# main.net
KiCad netlist of a schematic drawn in Altium Designer
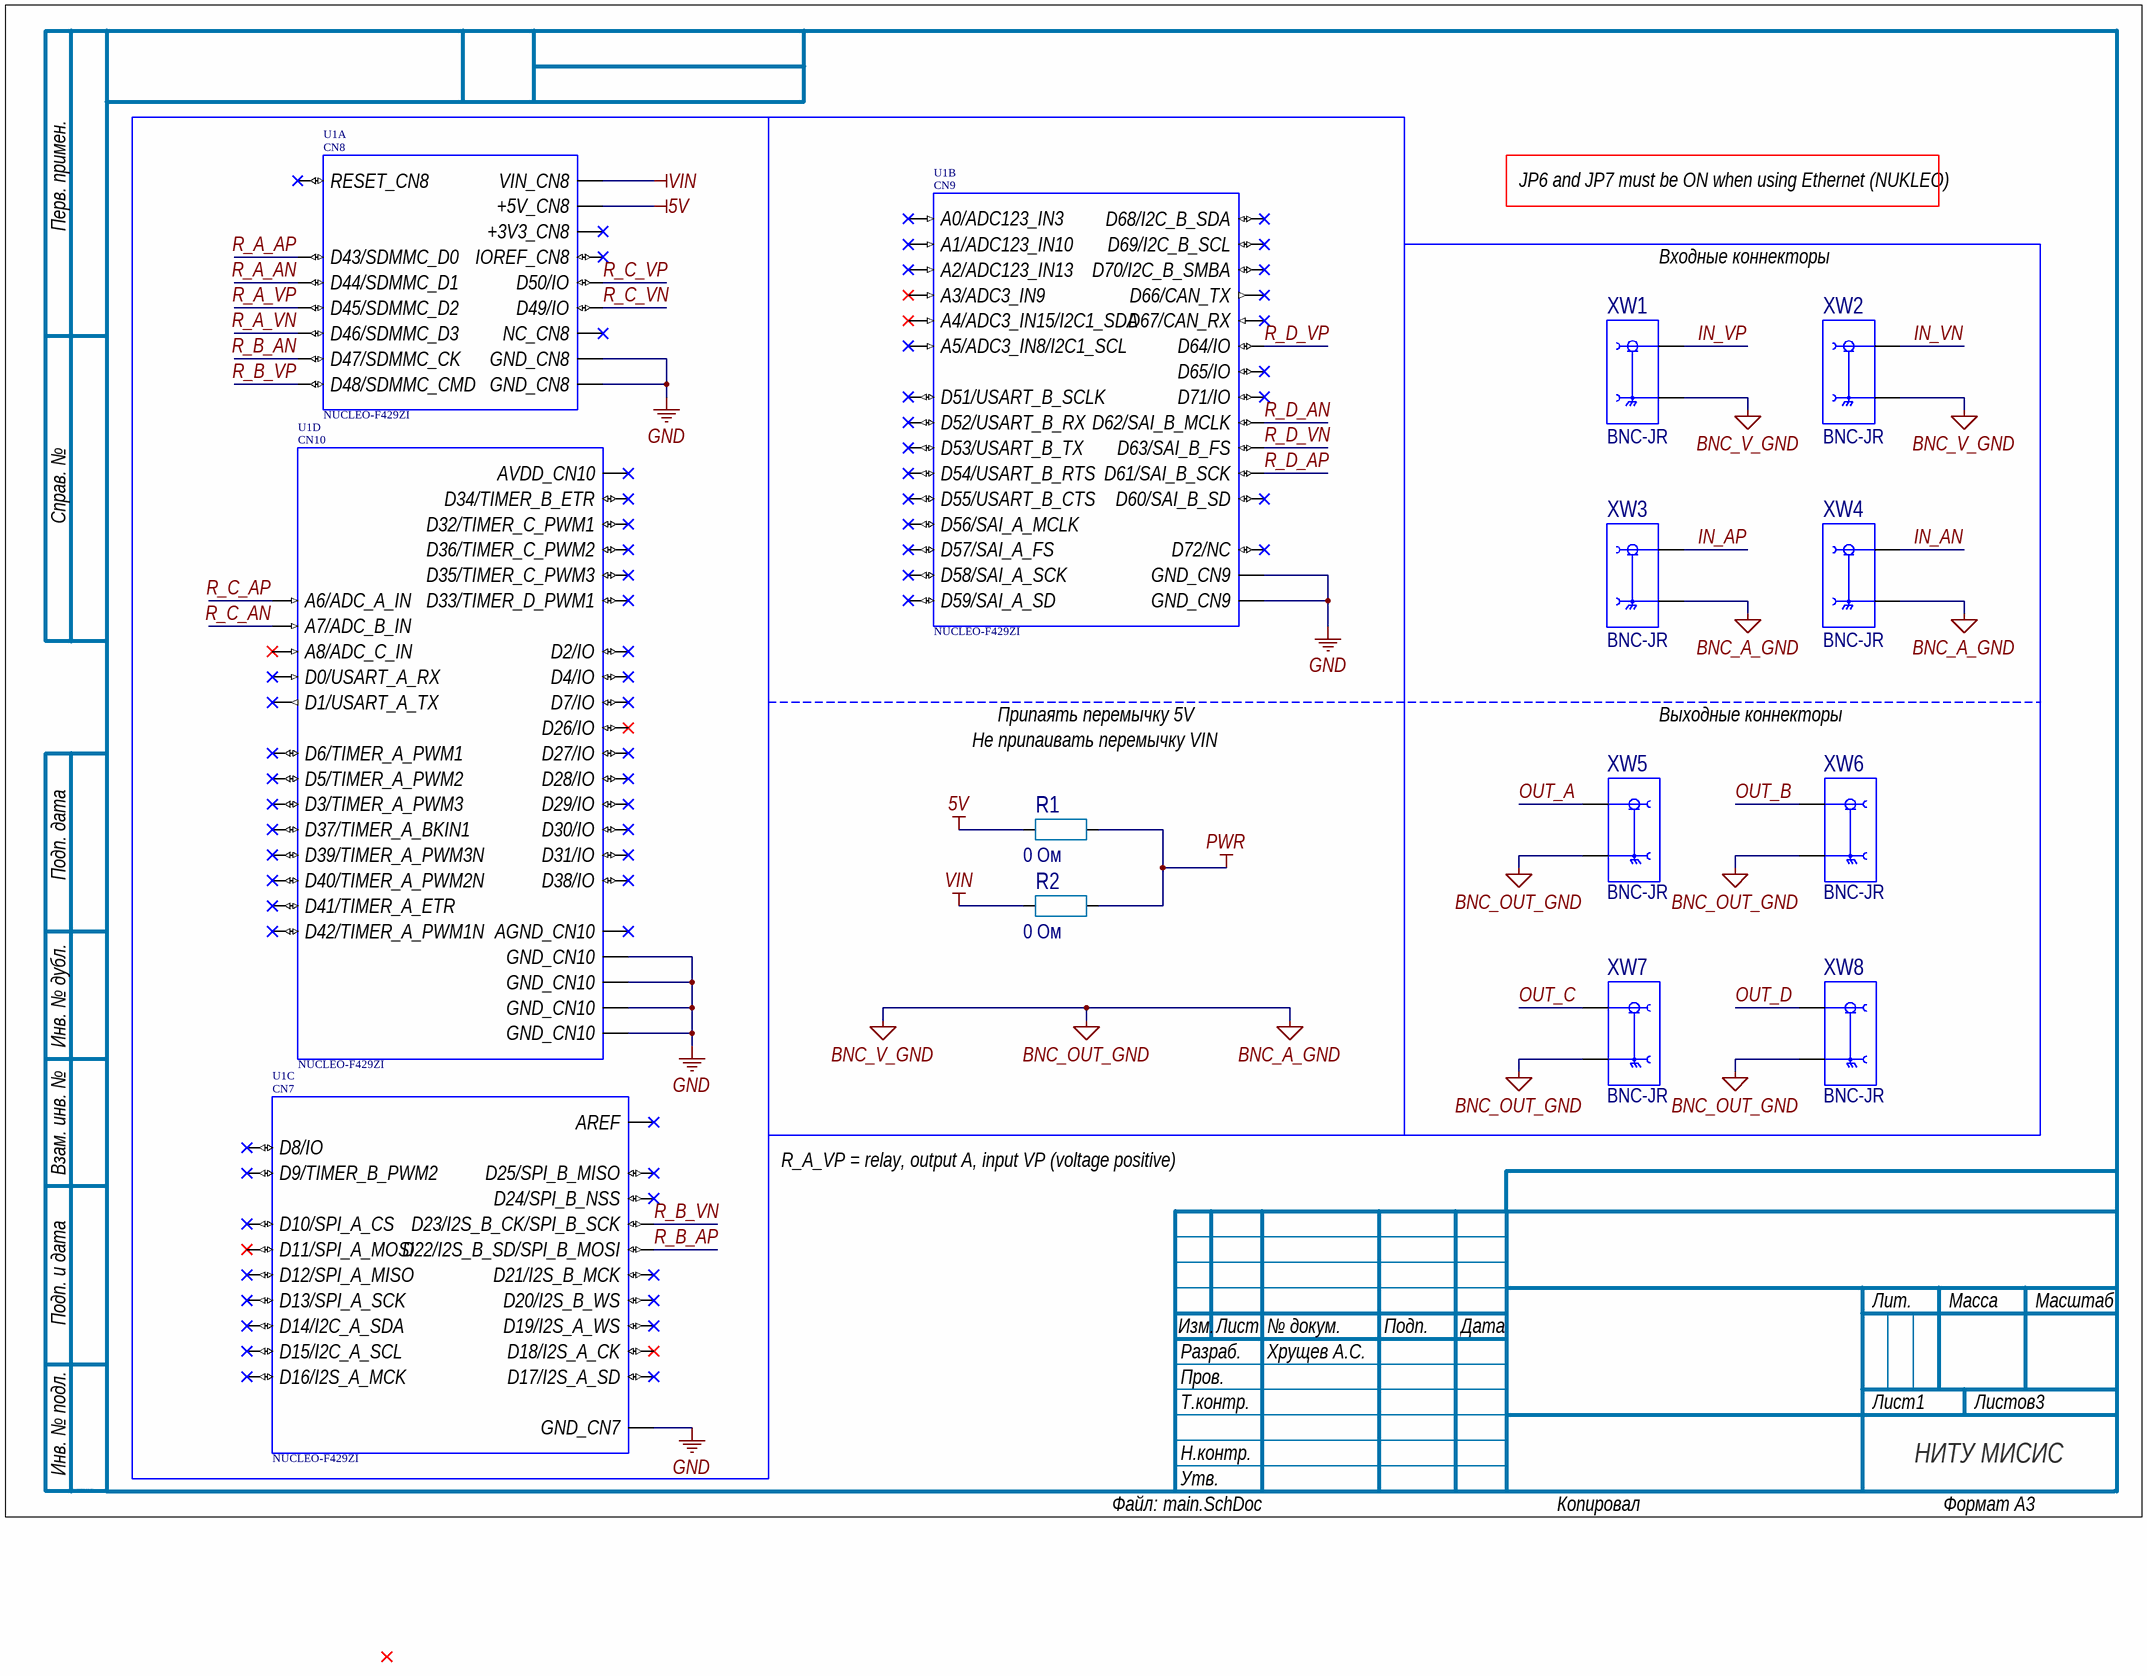
[diagram p0: main.SchDoc]

(export (version "E")
  (design (tool "Eeschema 10.0.6"))
  (components
    (comp (ref "R1")
      (value "0 Ом")
      (footprint "R0805")
      (description "Резистор 0 Ом")
      (libsource (lib "GOST_2.728_Rezistory&Kondensatory") (part "R1_POSTOYANNYJ"))
    )
    (comp (ref "R2")
      (value "0 Ом")
      (footprint "R0805")
      (description "Резистор 0 Ом")
      (libsource (lib "GOST_2.728_Rezistory&Kondensatory") (part "R1_POSTOYANNYJ"))
    )
    (comp (ref "U1")
      (value "NUCLEO-F429ZI")
      (footprint "MODULE_NUCLEO-F429ZI")
      (fields (field (name "MF") "STMicroelectronics"))
      (libsource (lib "NUCLEO-F429ZI") (part "NUCLEO-F429ZI"))
    )
    (comp (ref "XW1")
      (value "BNC-JR")
      (footprint "TE_227161-1")
      (description "Разъём высокочастотный RUICHI BNC-JR, гнездо на плату")
      (fields (field (name "MP") "227161-1"))
      (libsource (lib "") (part "BNC-JR_1"))
    )
    (comp (ref "XW2")
      (value "BNC-JR")
      (footprint "TE_227161-1")
      (description "Разъём высокочастотный RUICHI BNC-JR, гнездо на плату")
      (fields (field (name "MP") "227161-1"))
      (libsource (lib "") (part "BNC-JR_1"))
    )
    (comp (ref "XW3")
      (value "BNC-JR")
      (footprint "TE_227161-1")
      (description "Разъём высокочастотный RUICHI BNC-JR, гнездо на плату")
      (fields (field (name "MP") "227161-1"))
      (libsource (lib "") (part "BNC-JR_1"))
    )
    (comp (ref "XW4")
      (value "BNC-JR")
      (footprint "TE_227161-1")
      (description "Разъём высокочастотный RUICHI BNC-JR, гнездо на плату")
      (fields (field (name "MP") "227161-1"))
      (libsource (lib "") (part "BNC-JR_1"))
    )
    (comp (ref "XW5")
      (value "BNC-JR")
      (footprint "TE_227161-1")
      (description "Разъём высокочастотный RUICHI BNC-JR, гнездо на плату")
      (fields (field (name "MP") "227161-1"))
      (libsource (lib "BNC-JR") (part "BNC-JR"))
    )
    (comp (ref "XW6")
      (value "BNC-JR")
      (footprint "TE_227161-1")
      (description "Разъём высокочастотный RUICHI BNC-JR, гнездо на плату")
      (fields (field (name "MP") "227161-1"))
      (libsource (lib "BNC-JR") (part "BNC-JR"))
    )
    (comp (ref "XW7")
      (value "BNC-JR")
      (footprint "TE_227161-1")
      (description "Разъём высокочастотный RUICHI BNC-JR, гнездо на плату")
      (fields (field (name "MP") "227161-1"))
      (libsource (lib "BNC-JR") (part "BNC-JR"))
    )
    (comp (ref "XW8")
      (value "BNC-JR")
      (footprint "TE_227161-1")
      (description "Разъём высокочастотный RUICHI BNC-JR, гнездо на плату")
      (fields (field (name "MP") "227161-1"))
      (libsource (lib "BNC-JR") (part "BNC-JR"))
    )
  )
  (nets
    (net (code "1") (name "/IN_AN") (class "Default")
      (node (ref "XW4") (pin "1") (pinfunction "SIG_1") (pintype "passive"))
    )
    (net (code "2") (name "/IN_AP") (class "Default")
      (node (ref "XW3") (pin "1") (pinfunction "SIG_1") (pintype "passive"))
    )
    (net (code "3") (name "/IN_VN") (class "Default")
      (node (ref "XW2") (pin "1") (pinfunction "SIG_1") (pintype "passive"))
    )
    (net (code "4") (name "/IN_VP") (class "Default")
      (node (ref "XW1") (pin "1") (pinfunction "SIG_1") (pintype "passive"))
    )
    (net (code "5") (name "/OUT_A") (class "Default")
      (node (ref "XW5") (pin "1") (pinfunction "SIG_1") (pintype "passive"))
    )
    (net (code "6") (name "/OUT_B") (class "Default")
      (node (ref "XW6") (pin "1") (pinfunction "SIG_1") (pintype "passive"))
    )
    (net (code "7") (name "/OUT_C") (class "Default")
      (node (ref "XW7") (pin "1") (pinfunction "SIG_1") (pintype "passive"))
    )
    (net (code "8") (name "/OUT_D") (class "Default")
      (node (ref "XW8") (pin "1") (pinfunction "SIG_1") (pintype "passive"))
    )
    (net (code "9") (name "/R_A_AN") (class "Default")
      (node (ref "U1") (pin "CN8_4") (pinfunction "D44/SDMMC_D1_CN8_4") (pintype "bidirectional"))
    )
    (net (code "10") (name "/R_A_AP") (class "Default")
      (node (ref "U1") (pin "CN8_2") (pinfunction "D43/SDMMC_D0_CN8_2") (pintype "bidirectional"))
    )
    (net (code "11") (name "/R_A_VN") (class "Default")
      (node (ref "U1") (pin "CN8_8") (pinfunction "D46/SDMMC_D3_CN8_8") (pintype "bidirectional"))
    )
    (net (code "12") (name "/R_A_VP") (class "Default")
      (node (ref "U1") (pin "CN8_6") (pinfunction "D45/SDMMC_D2_CN8_6") (pintype "bidirectional"))
    )
    (net (code "13") (name "/R_B_AN") (class "Default")
      (node (ref "U1") (pin "CN8_10") (pinfunction "D47/SDMMC_CK_CN8_10") (pintype "bidirectional"))
    )
    (net (code "14") (name "/R_B_AP") (class "Default")
      (node (ref "U1") (pin "CN7_13") (pinfunction "D22/I2S_B_SD/SPI_B_MOSI_CN7_13") (pintype "bidirectional"))
    )
    (net (code "15") (name "/R_B_VN") (class "Default")
      (node (ref "U1") (pin "CN7_15") (pinfunction "D23/I2S_B_CK/SPI_B_SCK_CN7_15") (pintype "bidirectional"))
    )
    (net (code "16") (name "/R_B_VP") (class "Default")
      (node (ref "U1") (pin "CN8_12") (pinfunction "D48/SDMMC_CMD_CN8_12") (pintype "bidirectional"))
    )
    (net (code "17") (name "/R_C_AN") (class "Default")
      (node (ref "U1") (pin "CN10_9") (pinfunction "A7/ADC_B_IN_CN10_9") (pintype "input"))
    )
    (net (code "18") (name "/R_C_AP") (class "Default")
      (node (ref "U1") (pin "CN10_7") (pinfunction "A6/ADC_A_IN_CN10_7") (pintype "input"))
    )
    (net (code "19") (name "/R_C_VN") (class "Default")
      (node (ref "U1") (pin "CN8_14") (pinfunction "D49/IO_CN8_14") (pintype "bidirectional"))
    )
    (net (code "20") (name "/R_C_VP") (class "Default")
      (node (ref "U1") (pin "CN8_16") (pinfunction "D50/IO_CN8_16") (pintype "bidirectional"))
    )
    (net (code "21") (name "/R_D_AN") (class "Default")
      (node (ref "U1") (pin "CN9_26") (pinfunction "D62/SAI_B_MCLK_CN9_26") (pintype "bidirectional"))
    )
    (net (code "22") (name "/R_D_AP") (class "Default")
      (node (ref "U1") (pin "CN9_24") (pinfunction "D61/SAI_B_SCK_CN9_24") (pintype "bidirectional"))
    )
    (net (code "23") (name "/R_D_VN") (class "Default")
      (node (ref "U1") (pin "CN9_28") (pinfunction "D63/SAI_B_FS_CN9_28") (pintype "bidirectional"))
    )
    (net (code "24") (name "/R_D_VP") (class "Default")
      (node (ref "U1") (pin "CN9_30") (pinfunction "D64/IO_CN9_30") (pintype "bidirectional"))
    )
    (net (code "25") (name "5V") (class "Default")
      (node (ref "R1") (pin "1") (pinfunction "1_1") (pintype "passive"))
      (node (ref "U1") (pin "CN8_9") (pinfunction "+5V_CN8_CN8_9") (pintype "power_in"))
    )
    (net (code "26") (name "BNC_A_GND") (class "Default")
      (node (ref "XW1") (pin "2") (pinfunction "GND_2") (pintype "power_in"))
      (node (ref "XW2") (pin "2") (pinfunction "GND_2") (pintype "power_in"))
      (node (ref "XW3") (pin "2") (pinfunction "GND_2") (pintype "power_in"))
      (node (ref "XW4") (pin "2") (pinfunction "GND_2") (pintype "power_in"))
      (node (ref "XW5") (pin "2") (pinfunction "GND_2") (pintype "power_in"))
      (node (ref "XW6") (pin "2") (pinfunction "GND_2") (pintype "power_in"))
      (node (ref "XW7") (pin "2") (pinfunction "GND_2") (pintype "power_in"))
      (node (ref "XW8") (pin "2") (pinfunction "GND_2") (pintype "power_in"))
    )
    (net (code "27") (name "GND") (class "Default")
      (node (ref "U1") (pin "CN10_17") (pinfunction "GND_CN10_CN10_17") (pintype "power_in"))
      (node (ref "U1") (pin "CN10_22") (pinfunction "GND_CN10_CN10_22") (pintype "power_in"))
      (node (ref "U1") (pin "CN10_27") (pinfunction "GND_CN10_CN10_27") (pintype "power_in"))
      (node (ref "U1") (pin "CN10_5") (pinfunction "GND_CN10_CN10_5") (pintype "power_in"))
      (node (ref "U1") (pin "CN7_8") (pinfunction "GND_CN7_CN7_8") (pintype "power_in"))
      (node (ref "U1") (pin "CN8_11") (pinfunction "GND_CN8_CN8_11") (pintype "power_in"))
      (node (ref "U1") (pin "CN8_13") (pinfunction "GND_CN8_CN8_13") (pintype "power_in"))
      (node (ref "U1") (pin "CN9_12") (pinfunction "GND_CN9_CN9_12") (pintype "power_in"))
      (node (ref "U1") (pin "CN9_23") (pinfunction "GND_CN9_CN9_23") (pintype "power_in"))
    )
    (net (code "28") (name "PWR") (class "Default")
      (node (ref "R1") (pin "2") (pinfunction "2_2") (pintype "passive"))
      (node (ref "R2") (pin "2") (pinfunction "2_2") (pintype "passive"))
    )
    (net (code "29") (name "VIN") (class "Default")
      (node (ref "R2") (pin "1") (pinfunction "1_1") (pintype "passive"))
      (node (ref "U1") (pin "CN8_15") (pinfunction "VIN_CN8_CN8_15") (pintype "power_in"))
    )
    (net (code "30") (name "unconnected-(U1A-+3V3_CN8-PadCN8_7)") (class "Default")
      (node (ref "U1") (pin "CN8_7") (pinfunction "+3V3_CN8_CN8_7") (pintype "power_in+no_connect"))
    )
    (net (code "31") (name "unconnected-(U1A-IOREF_CN8-PadCN8_3)") (class "Default")
      (node (ref "U1") (pin "CN8_3") (pinfunction "IOREF_CN8_CN8_3") (pintype "bidirectional+no_connect"))
    )
    (net (code "32") (name "unconnected-(U1A-NC_CN8-PadCN8_1)") (class "Default")
      (node (ref "U1") (pin "CN8_1") (pinfunction "NC_CN8_CN8_1") (pintype "passive+no_connect"))
    )
    (net (code "33") (name "unconnected-(U1A-RESET_CN8-PadCN8_5)") (class "Default")
      (node (ref "U1") (pin "CN8_5") (pinfunction "RESET_CN8_CN8_5") (pintype "bidirectional+no_connect"))
    )
    (net (code "34") (name "unconnected-(U1B-A0{slash}ADC123_IN3-PadCN9_1)") (class "Default")
      (node (ref "U1") (pin "CN9_1") (pinfunction "A0/ADC123_IN3_CN9_1") (pintype "input+no_connect"))
    )
    (net (code "35") (name "unconnected-(U1B-A1{slash}ADC123_IN10-PadCN9_3)") (class "Default")
      (node (ref "U1") (pin "CN9_3") (pinfunction "A1/ADC123_IN10_CN9_3") (pintype "input+no_connect"))
    )
    (net (code "36") (name "unconnected-(U1B-A2{slash}ADC123_IN13-PadCN9_5)") (class "Default")
      (node (ref "U1") (pin "CN9_5") (pinfunction "A2/ADC123_IN13_CN9_5") (pintype "input+no_connect"))
    )
    (net (code "37") (name "unconnected-(U1B-A3{slash}ADC3_IN9-PadCN9_7)") (class "Default")
      (node (ref "U1") (pin "CN9_7") (pinfunction "A3/ADC3_IN9_CN9_7") (pintype "input+no_connect"))
    )
    (net (code "38") (name "unconnected-(U1B-A4{slash}ADC3_IN15{slash}I2C1_SDA-PadCN9_9)") (class "Default")
      (node (ref "U1") (pin "CN9_9") (pinfunction "A4/ADC3_IN15/I2C1_SDA_CN9_9") (pintype "input+no_connect"))
    )
    (net (code "39") (name "unconnected-(U1B-A5{slash}ADC3_IN8{slash}I2C1_SCL-PadCN9_11)") (class "Default")
      (node (ref "U1") (pin "CN9_11") (pinfunction "A5/ADC3_IN8/I2C1_SCL_CN9_11") (pintype "input+no_connect"))
    )
    (net (code "40") (name "unconnected-(U1B-D51{slash}USART_B_SCLK-PadCN9_2)") (class "Default")
      (node (ref "U1") (pin "CN9_2") (pinfunction "D51/USART_B_SCLK_CN9_2") (pintype "bidirectional+no_connect"))
    )
    (net (code "41") (name "unconnected-(U1B-D52{slash}USART_B_RX-PadCN9_4)") (class "Default")
      (node (ref "U1") (pin "CN9_4") (pinfunction "D52/USART_B_RX_CN9_4") (pintype "bidirectional+no_connect"))
    )
    (net (code "42") (name "unconnected-(U1B-D53{slash}USART_B_TX-PadCN9_6)") (class "Default")
      (node (ref "U1") (pin "CN9_6") (pinfunction "D53/USART_B_TX_CN9_6") (pintype "bidirectional+no_connect"))
    )
    (net (code "43") (name "unconnected-(U1B-D54{slash}USART_B_RTS-PadCN9_8)") (class "Default")
      (node (ref "U1") (pin "CN9_8") (pinfunction "D54/USART_B_RTS_CN9_8") (pintype "bidirectional+no_connect"))
    )
    (net (code "44") (name "unconnected-(U1B-D55{slash}USART_B_CTS-PadCN9_10)") (class "Default")
      (node (ref "U1") (pin "CN9_10") (pinfunction "D55/USART_B_CTS_CN9_10") (pintype "bidirectional+no_connect"))
    )
    (net (code "45") (name "unconnected-(U1B-D56{slash}SAI_A_MCLK-PadCN9_14)") (class "Default")
      (node (ref "U1") (pin "CN9_14") (pinfunction "D56/SAI_A_MCLK_CN9_14") (pintype "bidirectional+no_connect"))
    )
    (net (code "46") (name "unconnected-(U1B-D57{slash}SAI_A_FS-PadCN9_16)") (class "Default")
      (node (ref "U1") (pin "CN9_16") (pinfunction "D57/SAI_A_FS_CN9_16") (pintype "bidirectional+no_connect"))
    )
    (net (code "47") (name "unconnected-(U1B-D58{slash}SAI_A_SCK-PadCN9_18)") (class "Default")
      (node (ref "U1") (pin "CN9_18") (pinfunction "D58/SAI_A_SCK_CN9_18") (pintype "bidirectional+no_connect"))
    )
    (net (code "48") (name "unconnected-(U1B-D59{slash}SAI_A_SD-PadCN9_20)") (class "Default")
      (node (ref "U1") (pin "CN9_20") (pinfunction "D59/SAI_A_SD_CN9_20") (pintype "bidirectional+no_connect"))
    )
    (net (code "49") (name "unconnected-(U1B-D60{slash}SAI_B_SD-PadCN9_22)") (class "Default")
      (node (ref "U1") (pin "CN9_22") (pinfunction "D60/SAI_B_SD_CN9_22") (pintype "bidirectional+no_connect"))
    )
    (net (code "50") (name "unconnected-(U1B-D65{slash}IO-PadCN9_29)") (class "Default")
      (node (ref "U1") (pin "CN9_29") (pinfunction "D65/IO_CN9_29") (pintype "bidirectional+no_connect"))
    )
    (net (code "51") (name "unconnected-(U1B-D66{slash}CAN_TX-PadCN9_27)") (class "Default")
      (node (ref "U1") (pin "CN9_27") (pinfunction "D66/CAN_TX_CN9_27") (pintype "output+no_connect"))
    )
    (net (code "52") (name "unconnected-(U1B-D67{slash}CAN_RX-PadCN9_25)") (class "Default")
      (node (ref "U1") (pin "CN9_25") (pinfunction "D67/CAN_RX_CN9_25") (pintype "input+no_connect"))
    )
    (net (code "53") (name "unconnected-(U1B-D68{slash}I2C_B_SDA-PadCN9_21)") (class "Default")
      (node (ref "U1") (pin "CN9_21") (pinfunction "D68/I2C_B_SDA_CN9_21") (pintype "bidirectional+no_connect"))
    )
    (net (code "54") (name "unconnected-(U1B-D69{slash}I2C_B_SCL-PadCN9_19)") (class "Default")
      (node (ref "U1") (pin "CN9_19") (pinfunction "D69/I2C_B_SCL_CN9_19") (pintype "bidirectional+no_connect"))
    )
    (net (code "55") (name "unconnected-(U1B-D70{slash}I2C_B_SMBA-PadCN9_17)") (class "Default")
      (node (ref "U1") (pin "CN9_17") (pinfunction "D70/I2C_B_SMBA_CN9_17") (pintype "bidirectional+no_connect"))
    )
    (net (code "56") (name "unconnected-(U1B-D71{slash}IO-PadCN9_15)") (class "Default")
      (node (ref "U1") (pin "CN9_15") (pinfunction "D71/IO_CN9_15") (pintype "bidirectional+no_connect"))
    )
    (net (code "57") (name "unconnected-(U1B-D72{slash}NC-PadCN9_13)") (class "Default")
      (node (ref "U1") (pin "CN9_13") (pinfunction "D72/NC_CN9_13") (pintype "bidirectional+no_connect"))
    )
    (net (code "58") (name "unconnected-(U1C-AREF-PadCN7_6)") (class "Default")
      (node (ref "U1") (pin "CN7_6") (pinfunction "AREF_CN7_6") (pintype "power_in+no_connect"))
    )
    (net (code "59") (name "unconnected-(U1C-D8{slash}IO-PadCN7_20)") (class "Default")
      (node (ref "U1") (pin "CN7_20") (pinfunction "D8/IO_CN7_20") (pintype "bidirectional+no_connect"))
    )
    (net (code "60") (name "unconnected-(U1C-D9{slash}TIMER_B_PWM2-PadCN7_18)") (class "Default")
      (node (ref "U1") (pin "CN7_18") (pinfunction "D9/TIMER_B_PWM2_CN7_18") (pintype "bidirectional+no_connect"))
    )
    (net (code "61") (name "unconnected-(U1C-D10{slash}SPI_A_CS-PadCN7_16)") (class "Default")
      (node (ref "U1") (pin "CN7_16") (pinfunction "D10/SPI_A_CS_CN7_16") (pintype "bidirectional+no_connect"))
    )
    (net (code "62") (name "unconnected-(U1C-D11{slash}SPI_A_MOSI-PadCN7_14)") (class "Default")
      (node (ref "U1") (pin "CN7_14") (pinfunction "D11/SPI_A_MOSI_CN7_14") (pintype "bidirectional+no_connect"))
    )
    (net (code "63") (name "unconnected-(U1C-D12{slash}SPI_A_MISO-PadCN7_12)") (class "Default")
      (node (ref "U1") (pin "CN7_12") (pinfunction "D12/SPI_A_MISO_CN7_12") (pintype "bidirectional+no_connect"))
    )
    (net (code "64") (name "unconnected-(U1C-D13{slash}SPI_A_SCK-PadCN7_10)") (class "Default")
      (node (ref "U1") (pin "CN7_10") (pinfunction "D13/SPI_A_SCK_CN7_10") (pintype "bidirectional+no_connect"))
    )
    (net (code "65") (name "unconnected-(U1C-D14{slash}I2C_A_SDA-PadCN7_4)") (class "Default")
      (node (ref "U1") (pin "CN7_4") (pinfunction "D14/I2C_A_SDA_CN7_4") (pintype "bidirectional+no_connect"))
    )
    (net (code "66") (name "unconnected-(U1C-D15{slash}I2C_A_SCL-PadCN7_2)") (class "Default")
      (node (ref "U1") (pin "CN7_2") (pinfunction "D15/I2C_A_SCL_CN7_2") (pintype "bidirectional+no_connect"))
    )
    (net (code "67") (name "unconnected-(U1C-D16{slash}I2S_A_MCK-PadCN7_1)") (class "Default")
      (node (ref "U1") (pin "CN7_1") (pinfunction "D16/I2S_A_MCK_CN7_1") (pintype "bidirectional+no_connect"))
    )
    (net (code "68") (name "unconnected-(U1C-D17{slash}I2S_A_SD-PadCN7_3)") (class "Default")
      (node (ref "U1") (pin "CN7_3") (pinfunction "D17/I2S_A_SD_CN7_3") (pintype "bidirectional+no_connect"))
    )
    (net (code "69") (name "unconnected-(U1C-D18{slash}I2S_A_CK-PadCN7_5)") (class "Default")
      (node (ref "U1") (pin "CN7_5") (pinfunction "D18/I2S_A_CK_CN7_5") (pintype "bidirectional+no_connect"))
    )
    (net (code "70") (name "unconnected-(U1C-D19{slash}I2S_A_WS-PadCN7_7)") (class "Default")
      (node (ref "U1") (pin "CN7_7") (pinfunction "D19/I2S_A_WS_CN7_7") (pintype "bidirectional+no_connect"))
    )
    (net (code "71") (name "unconnected-(U1C-D20{slash}I2S_B_WS-PadCN7_9)") (class "Default")
      (node (ref "U1") (pin "CN7_9") (pinfunction "D20/I2S_B_WS_CN7_9") (pintype "bidirectional+no_connect"))
    )
    (net (code "72") (name "unconnected-(U1C-D21{slash}I2S_B_MCK-PadCN7_11)") (class "Default")
      (node (ref "U1") (pin "CN7_11") (pinfunction "D21/I2S_B_MCK_CN7_11") (pintype "bidirectional+no_connect"))
    )
    (net (code "73") (name "unconnected-(U1C-D24{slash}SPI_B_NSS-PadCN7_17)") (class "Default")
      (node (ref "U1") (pin "CN7_17") (pinfunction "D24/SPI_B_NSS_CN7_17") (pintype "bidirectional+no_connect"))
    )
    (net (code "74") (name "unconnected-(U1C-D25{slash}SPI_B_MISO-PadCN7_19)") (class "Default")
      (node (ref "U1") (pin "CN7_19") (pinfunction "D25/SPI_B_MISO_CN7_19") (pintype "bidirectional+no_connect"))
    )
    (net (code "75") (name "unconnected-(U1D-A8{slash}ADC_C_IN-PadCN10_11)") (class "Default")
      (node (ref "U1") (pin "CN10_11") (pinfunction "A8/ADC_C_IN_CN10_11") (pintype "input+no_connect"))
    )
    (net (code "76") (name "unconnected-(U1D-AGND_CN10-PadCN10_3)") (class "Default")
      (node (ref "U1") (pin "CN10_3") (pinfunction "AGND_CN10_CN10_3") (pintype "power_in+no_connect"))
    )
    (net (code "77") (name "unconnected-(U1D-AVDD_CN10-PadCN10_1)") (class "Default")
      (node (ref "U1") (pin "CN10_1") (pinfunction "AVDD_CN10_CN10_1") (pintype "power_in+no_connect"))
    )
    (net (code "78") (name "unconnected-(U1D-D0{slash}USART_A_RX-PadCN10_16)") (class "Default")
      (node (ref "U1") (pin "CN10_16") (pinfunction "D0/USART_A_RX_CN10_16") (pintype "input+no_connect"))
    )
    (net (code "79") (name "unconnected-(U1D-D1{slash}USART_A_TX-PadCN10_14)") (class "Default")
      (node (ref "U1") (pin "CN10_14") (pinfunction "D1/USART_A_TX_CN10_14") (pintype "output+no_connect"))
    )
    (net (code "80") (name "unconnected-(U1D-D2{slash}IO-PadCN10_12)") (class "Default")
      (node (ref "U1") (pin "CN10_12") (pinfunction "D2/IO_CN10_12") (pintype "bidirectional+no_connect"))
    )
    (net (code "81") (name "unconnected-(U1D-D3{slash}TIMER_A_PWM3-PadCN10_10)") (class "Default")
      (node (ref "U1") (pin "CN10_10") (pinfunction "D3/TIMER_A_PWM3_CN10_10") (pintype "bidirectional+no_connect"))
    )
    (net (code "82") (name "unconnected-(U1D-D4{slash}IO-PadCN10_8)") (class "Default")
      (node (ref "U1") (pin "CN10_8") (pinfunction "D4/IO_CN10_8") (pintype "bidirectional+no_connect"))
    )
    (net (code "83") (name "unconnected-(U1D-D5{slash}TIMER_A_PWM2-PadCN10_6)") (class "Default")
      (node (ref "U1") (pin "CN10_6") (pinfunction "D5/TIMER_A_PWM2_CN10_6") (pintype "bidirectional+no_connect"))
    )
    (net (code "84") (name "unconnected-(U1D-D6{slash}TIMER_A_PWM1-PadCN10_4)") (class "Default")
      (node (ref "U1") (pin "CN10_4") (pinfunction "D6/TIMER_A_PWM1_CN10_4") (pintype "bidirectional+no_connect"))
    )
    (net (code "85") (name "unconnected-(U1D-D7{slash}IO-PadCN10_2)") (class "Default")
      (node (ref "U1") (pin "CN10_2") (pinfunction "D7/IO_CN10_2") (pintype "bidirectional+no_connect"))
    )
    (net (code "86") (name "unconnected-(U1D-D26{slash}IO-PadCN10_13)") (class "Default")
      (node (ref "U1") (pin "CN10_13") (pinfunction "D26/IO_CN10_13") (pintype "bidirectional+no_connect"))
    )
    (net (code "87") (name "unconnected-(U1D-D27{slash}IO-PadCN10_15)") (class "Default")
      (node (ref "U1") (pin "CN10_15") (pinfunction "D27/IO_CN10_15") (pintype "bidirectional+no_connect"))
    )
    (net (code "88") (name "unconnected-(U1D-D28{slash}IO-PadCN10_19)") (class "Default")
      (node (ref "U1") (pin "CN10_19") (pinfunction "D28/IO_CN10_19") (pintype "bidirectional+no_connect"))
    )
    (net (code "89") (name "unconnected-(U1D-D29{slash}IO-PadCN10_21)") (class "Default")
      (node (ref "U1") (pin "CN10_21") (pinfunction "D29/IO_CN10_21") (pintype "bidirectional+no_connect"))
    )
    (net (code "90") (name "unconnected-(U1D-D30{slash}IO-PadCN10_23)") (class "Default")
      (node (ref "U1") (pin "CN10_23") (pinfunction "D30/IO_CN10_23") (pintype "bidirectional+no_connect"))
    )
    (net (code "91") (name "unconnected-(U1D-D31{slash}IO-PadCN10_25)") (class "Default")
      (node (ref "U1") (pin "CN10_25") (pinfunction "D31/IO_CN10_25") (pintype "bidirectional+no_connect"))
    )
    (net (code "92") (name "unconnected-(U1D-D32{slash}TIMER_C_PWM1-PadCN10_29)") (class "Default")
      (node (ref "U1") (pin "CN10_29") (pinfunction "D32/TIMER_C_PWM1_CN10_29") (pintype "bidirectional+no_connect"))
    )
    (net (code "93") (name "unconnected-(U1D-D33{slash}TIMER_D_PWM1-PadCN10_31)") (class "Default")
      (node (ref "U1") (pin "CN10_31") (pinfunction "D33/TIMER_D_PWM1_CN10_31") (pintype "bidirectional+no_connect"))
    )
    (net (code "94") (name "unconnected-(U1D-D34{slash}TIMER_B_ETR-PadCN10_33)") (class "Default")
      (node (ref "U1") (pin "CN10_33") (pinfunction "D34/TIMER_B_ETR_CN10_33") (pintype "bidirectional+no_connect"))
    )
    (net (code "95") (name "unconnected-(U1D-D35{slash}TIMER_C_PWM3-PadCN10_34)") (class "Default")
      (node (ref "U1") (pin "CN10_34") (pinfunction "D35/TIMER_C_PWM3_CN10_34") (pintype "bidirectional+no_connect"))
    )
    (net (code "96") (name "unconnected-(U1D-D36{slash}TIMER_C_PWM2-PadCN10_32)") (class "Default")
      (node (ref "U1") (pin "CN10_32") (pinfunction "D36/TIMER_C_PWM2_CN10_32") (pintype "bidirectional+no_connect"))
    )
    (net (code "97") (name "unconnected-(U1D-D37{slash}TIMER_A_BKIN1-PadCN10_30)") (class "Default")
      (node (ref "U1") (pin "CN10_30") (pinfunction "D37/TIMER_A_BKIN1_CN10_30") (pintype "bidirectional+no_connect"))
    )
    (net (code "98") (name "unconnected-(U1D-D38{slash}IO-PadCN10_28)") (class "Default")
      (node (ref "U1") (pin "CN10_28") (pinfunction "D38/IO_CN10_28") (pintype "bidirectional+no_connect"))
    )
    (net (code "99") (name "unconnected-(U1D-D39{slash}TIMER_A_PWM3N-PadCN10_26)") (class "Default")
      (node (ref "U1") (pin "CN10_26") (pinfunction "D39/TIMER_A_PWM3N_CN10_26") (pintype "bidirectional+no_connect"))
    )
    (net (code "100") (name "unconnected-(U1D-D40{slash}TIMER_A_PWM2N-PadCN10_24)") (class "Default")
      (node (ref "U1") (pin "CN10_24") (pinfunction "D40/TIMER_A_PWM2N_CN10_24") (pintype "bidirectional+no_connect"))
    )
    (net (code "101") (name "unconnected-(U1D-D41{slash}TIMER_A_ETR-PadCN10_20)") (class "Default")
      (node (ref "U1") (pin "CN10_20") (pinfunction "D41/TIMER_A_ETR_CN10_20") (pintype "bidirectional+no_connect"))
    )
    (net (code "102") (name "unconnected-(U1D-D42{slash}TIMER_A_PWM1N-PadCN10_18)") (class "Default")
      (node (ref "U1") (pin "CN10_18") (pinfunction "D42/TIMER_A_PWM1N_CN10_18") (pintype "bidirectional+no_connect"))
    )
  )
)
